# CTR-Lower-Main-Board-Rev-C-Power.net
KiCad netlist of a schematic drawn in Altium Designer
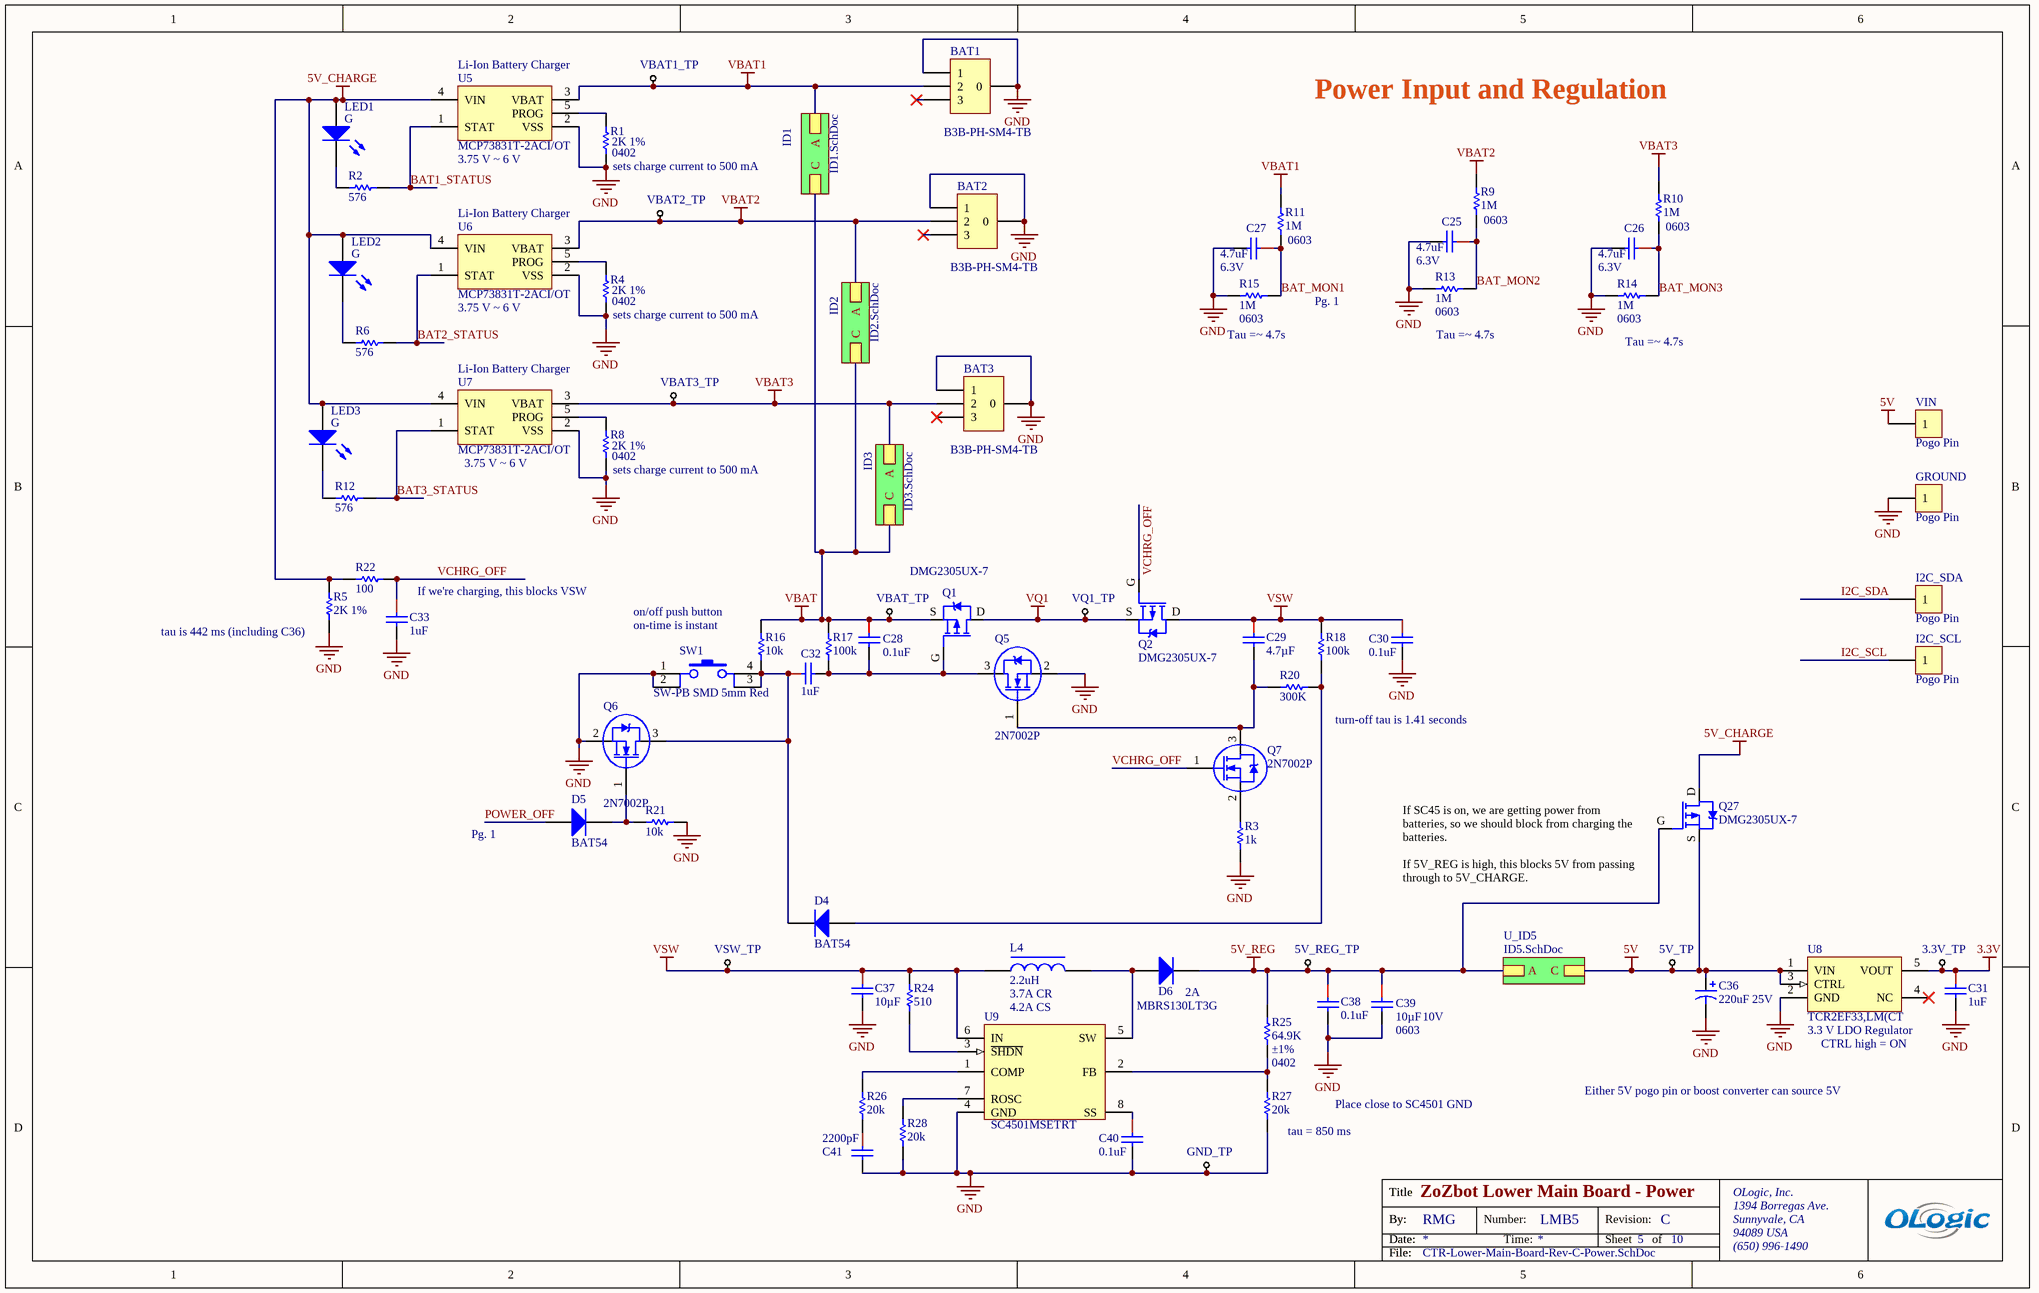
[diagram p0: CTR-Lower-Main-Board-Rev-C-Power.SchDoc]

(export (version "E")
  (design (tool "Eeschema 10.0.6"))
  (components
    (comp (ref "3.3V_TP")
      (value "Test Point")
      (footprint "TestPoint-TH 42 mil")
      (libsource (lib "OLogic-Misc") (part "TestPoint, small"))
    )
    (comp (ref "5V_REG_TP")
      (value "Test Point")
      (footprint "TestPoint-TH 42 mil")
      (libsource (lib "OLogic-Misc") (part "TestPoint, small"))
    )
    (comp (ref "5V_TP")
      (value "Test Point")
      (footprint "TestPoint-TH 42 mil")
      (libsource (lib "OLogic-Misc") (part "TestPoint, small"))
    )
    (comp (ref "BAT1")
      (value "B3B-PH-SM4-TB")
      (footprint "JST-B3B-PH-SM4-TB")
      (description "2mm Locking Header, 3-Pin")
      (fields
        (field (name "MANUFACTURER") "JST Sales America Inc")
        (field (name "MANUFACTURER PART NUMBER") "B3B-PH-SM4-TB(LF)(SN)(P)")
      )
      (libsource (lib "OLogic-Connectors") (part "JST-B3B-PH-SM4-TB"))
    )
    (comp (ref "BAT2")
      (value "B3B-PH-SM4-TB")
      (footprint "JST-B3B-PH-SM4-TB")
      (description "2mm Locking Header, 3-Pin")
      (fields
        (field (name "MANUFACTURER") "JST Sales America Inc")
        (field (name "MANUFACTURER PART NUMBER") "B3B-PH-SM4-TB(LF)(SN)(P)")
      )
      (libsource (lib "OLogic-Connectors") (part "JST-B3B-PH-SM4-TB"))
    )
    (comp (ref "BAT3")
      (value "B3B-PH-SM4-TB")
      (footprint "JST-B3B-PH-SM4-TB")
      (description "2mm Locking Header, 3-Pin")
      (fields
        (field (name "MANUFACTURER") "JST Sales America Inc")
        (field (name "MANUFACTURER PART NUMBER") "B3B-PH-SM4-TB(LF)(SN)(P)")
      )
      (libsource (lib "OLogic-Connectors") (part "JST-B3B-PH-SM4-TB"))
    )
    (comp (ref "C25")
      (value "4.7uF")
      (footprint "CAPC0402(1005)_N")
      (description "4.7uF 0402")
      (fields
        (field (name "MANUFACTURER") "Murata Electronics North America")
        (field (name "MANUFACTURER PART NUMBER") "GRM155R60J475ME47D")
        (field (name "VOLTAGE - RATED") "6.3V")
      )
      (libsource (lib "OLogic-Passive") (part "CAP CER 4.7UF 6.3V 10% X5R 0402"))
    )
    (comp (ref "C26")
      (value "4.7uF")
      (footprint "CAPC0402(1005)_N")
      (description "4.7uF 0402")
      (fields
        (field (name "MANUFACTURER") "Murata Electronics North America")
        (field (name "MANUFACTURER PART NUMBER") "GRM155R60J475ME47D")
        (field (name "VOLTAGE - RATED") "6.3V")
      )
      (libsource (lib "OLogic-Passive") (part "CAP CER 4.7UF 6.3V 10% X5R 0402"))
    )
    (comp (ref "C27")
      (value "4.7uF")
      (footprint "CAPC0402(1005)_N")
      (description "4.7uF 0402")
      (fields
        (field (name "MANUFACTURER") "Murata Electronics North America")
        (field (name "MANUFACTURER PART NUMBER") "GRM155R60J475ME47D")
        (field (name "VOLTAGE - RATED") "6.3V")
      )
      (libsource (lib "OLogic-Passive") (part "CAP CER 4.7UF 6.3V 10% X5R 0402"))
    )
    (comp (ref "C28")
      (value "0.1uF")
      (footprint "CAPC0402(1005)_N")
      (description "0.1uF 0402 50V")
      (fields
        (field (name "MANUFACTURER") "TDK Corporation")
        (field (name "MANUFACTURER PART NUMBER") "CGA2B3X7R1H104K050BB")
        (field (name "CREATOR") "osman")
      )
      (libsource (lib "OLogic-Passive") (part "CAP CER 0.1UF 50V 10% X7R 0402"))
    )
    (comp (ref "C29")
      (value "4.7UF 0603")
      (footprint "CAPC0603(1608)_L")
      (fields
        (field (name "MANUFACTURER") "Taiyo Yuden")
        (field (name "MANUFACTURER PART NUMBER") "EMK107ABJ475KA-T")
        (field (name "TOLERANCE") "±10%")
        (field (name "CAPACITANCE") "4.7µF")
        (field (name "CREATOR") "osman")
      )
      (libsource (lib "OLogic-Passive") (part "CAP CER 4.7UF 16V 10% X5R 0603"))
    )
    (comp (ref "C30")
      (value "0.1uF")
      (footprint "CAPC0402(1005)_N")
      (description "0.1uF 0402 50V")
      (fields
        (field (name "MANUFACTURER") "TDK Corporation")
        (field (name "MANUFACTURER PART NUMBER") "CGA2B3X7R1H104K050BB")
        (field (name "CREATOR") "osman")
      )
      (libsource (lib "OLogic-Passive") (part "CAP CER 0.1UF 50V 10% X7R 0402"))
    )
    (comp (ref "C31")
      (value "1uF")
      (footprint "CAPC0402(1005)_N")
      (description "1UF 0402")
      (fields
        (field (name "MANUFACTURER") "TDK Corporation")
        (field (name "MANUFACTURER PART NUMBER") "C1005X5R1C105K050BC")
      )
      (libsource (lib "OLogic-Passive") (part "CAP CER 1UF 16V 10% X5R 0402"))
    )
    (comp (ref "C32")
      (value "1uF")
      (footprint "CAPC0402(1005)_N")
      (description "1UF 0402")
      (fields
        (field (name "MANUFACTURER") "TDK Corporation")
        (field (name "MANUFACTURER PART NUMBER") "C1005X5R1C105K050BC")
      )
      (libsource (lib "OLogic-Passive") (part "CAP CER 1UF 16V 10% X5R 0402"))
    )
    (comp (ref "C33")
      (value "1uF")
      (footprint "CAPC0402(1005)_N")
      (description "1UF 0402")
      (fields
        (field (name "MANUFACTURER") "TDK Corporation")
        (field (name "MANUFACTURER PART NUMBER") "C1005X5R1C105K050BC")
      )
      (libsource (lib "OLogic-Passive") (part "CAP CER 1UF 16V 10% X5R 0402"))
    )
    (comp (ref "C36")
      (value "220uF 25V")
      (footprint "U2-P-M")
      (description "220uF 25V CAN")
      (fields
        (field (name "MANUFACTURER") "Nichicon")
        (field (name "MANUFACTURER PART NUMBER") "UWT1E221MNL1GS")
      )
      (libsource (lib "OLogic-Passive") (part "CAP ALUM 220UF 25V 20% SMD CHEAPER"))
    )
    (comp (ref "C37")
      (value "CAP 10UF 10V 10% X5R 0603")
      (footprint "CAPC0603(1608)_N")
      (description "10uF 0603")
      (fields
        (field (name "MANUFACTURER") "Samsung Electro-Mechanics America, Inc")
        (field (name "MANUFACTURER PART NUMBER") "CL10A106KP8NNNC")
        (field (name "CAPACITANCE") "10µF")
        (field (name "CREATOR") "osman")
      )
      (libsource (lib "OLogic-Passive") (part "CAP 10UF 10V 10% X5R 0603"))
    )
    (comp (ref "C38")
      (value "0.1uF")
      (footprint "CAPC0402(1005)_N")
      (description "0.1uF 0402 50V")
      (fields
        (field (name "MANUFACTURER") "TDK Corporation")
        (field (name "MANUFACTURER PART NUMBER") "CGA2B3X7R1H104K050BB")
        (field (name "CREATOR") "osman")
      )
      (libsource (lib "OLogic-Passive") (part "CAP CER 0.1UF 50V 10% X7R 0402"))
    )
    (comp (ref "C39")
      (value "CAP 10UF 10V 10% X5R 0603")
      (footprint "CAPC0603(1608)_N")
      (description "10uF 0603")
      (fields
        (field (name "MANUFACTURER") "Samsung Electro-Mechanics America, Inc")
        (field (name "MANUFACTURER PART NUMBER") "CL10A106KP8NNNC")
        (field (name "VOLTAGE - RATED") "10V")
        (field (name "PACKAGE / CASE") "0603")
        (field (name "CAPACITANCE") "10µF")
        (field (name "CREATOR") "osman")
      )
      (libsource (lib "OLogic-Passive") (part "CAP 10UF 10V 10% X5R 0603"))
    )
    (comp (ref "C40")
      (value "0.1uF")
      (footprint "CAPC0402(1005)_N")
      (description "0.1uF 0402 50V")
      (fields
        (field (name "MANUFACTURER") "TDK Corporation")
        (field (name "MANUFACTURER PART NUMBER") "CGA2B3X7R1H104K050BB")
        (field (name "CREATOR") "osman")
      )
      (libsource (lib "OLogic-Passive") (part "CAP CER 0.1UF 50V 10% X7R 0402"))
    )
    (comp (ref "C41")
      (value "2200pF")
      (footprint "CAPC0402(1005)_N")
      (description "2200pF 0402")
      (fields
        (field (name "MANUFACTURER") "Yageo")
        (field (name "MANUFACTURER PART NUMBER") "CC0402KRX7R9BB222")
        (field (name "CAPACITANCE") "2200pF")
        (field (name "CREATOR") "osman")
      )
      (libsource (lib "OLogic-Passive") (part "CAP CER 2200PF 50V 10% X7R 0402"))
    )
    (comp (ref "D4")
      (value "BAT54")
      (footprint "SOT23")
      (description "Schottky Barrier Diode")
      (fields (field (name "MANUFACTURER") "Fairchild"))
      (libsource (lib "OLogic-Diode-Opto-LED") (part "BAT54"))
    )
    (comp (ref "D5")
      (value "BAT54")
      (footprint "SOT23")
      (description "Schottky Barrier Diode")
      (fields (field (name "MANUFACTURER") "Fairchild"))
      (libsource (lib "OLogic-Diode-Opto-LED") (part "BAT54"))
    )
    (comp (ref "D6")
      (value "MBRS130LT3")
      (footprint "DO-214AA")
      (description "Schottky Barrier Rectifier 1A 30V")
      (fields
        (field (name "MANUFACTURER") "ON Semiconductor")
        (field (name "MANUFACTURER PART NUMBER") "MBRS130LT3G")
        (field (name "CURRENT - AVERAGE RECTIFIED (IO)") "2A")
      )
      (libsource (lib "OLogic-Diode-Opto-LED") (part "MBRS130LT3"))
    )
    (comp (ref "GND_TP")
      (value "Test Point")
      (footprint "TestPoint-TH 42 mil")
      (libsource (lib "OLogic-Misc") (part "TestPoint, small"))
    )
    (comp (ref "GROUND")
      (value "Pogo Pin")
      (footprint "POGO_PIN")
      (fields
        (field (name "MANUFACTURER") "Mill-Max Manufacturing Corp.")
        (field (name "MANUFACTURER PART NUMBER") "0850-0-15-20-83-14-11-0")
      )
      (libsource (lib "OLogic-Connectors") (part "0850-0-15-20-83-14-11-0"))
    )
    (comp (ref "I2C_SCL")
      (value "Pogo Pin")
      (footprint "POGO_PIN")
      (fields
        (field (name "MANUFACTURER") "Mill-Max Manufacturing Corp.")
        (field (name "MANUFACTURER PART NUMBER") "0850-0-15-20-83-14-11-0")
      )
      (libsource (lib "OLogic-Connectors") (part "0850-0-15-20-83-14-11-0"))
    )
    (comp (ref "I2C_SDA")
      (value "Pogo Pin")
      (footprint "POGO_PIN")
      (fields
        (field (name "MANUFACTURER") "Mill-Max Manufacturing Corp.")
        (field (name "MANUFACTURER PART NUMBER") "0850-0-15-20-83-14-11-0")
      )
      (libsource (lib "OLogic-Connectors") (part "0850-0-15-20-83-14-11-0"))
    )
    (comp (ref "L4")
      (value "2.2uH")
      (footprint "IND_TAIYO_NR6028")
      (description "2.2uH 6x6mm")
      (fields
        (field (name "MANUFACTURER") "Taiyo Yuden")
        (field (name "MANUFACTURER PART NUMBER") "NR6028T2R2N")
        (field (name "CURRENT RATING") "3.7A CR")
        (field (name "CURRENT - SATURATION") "4.2A CS")
      )
      (libsource (lib "OLogic-Passive") (part "INDUCTOR 2.2UH 4.2A 30% SMD"))
    )
    (comp (ref "LED1")
      (value "G")
      (footprint "SM-LED-0603")
      (description "0603 SMD GREEN LED")
      (fields
        (field (name "MANUFACTURER") "Lite-On Inc")
        (field (name "MANUFACTURER PART NUMBER") "LTST-C191KGKT")
      )
      (libsource (lib "OLogic-Diode-Opto-LED") (part "LED GREEN CLEAR THIN 0603 SMD"))
    )
    (comp (ref "LED2")
      (value "G")
      (footprint "SM-LED-0603")
      (description "0603 SMD GREEN LED")
      (fields
        (field (name "MANUFACTURER") "Lite-On Inc")
        (field (name "MANUFACTURER PART NUMBER") "LTST-C191KGKT")
      )
      (libsource (lib "OLogic-Diode-Opto-LED") (part "LED GREEN CLEAR THIN 0603 SMD"))
    )
    (comp (ref "LED3")
      (value "G")
      (footprint "SM-LED-0603")
      (description "0603 SMD GREEN LED")
      (fields
        (field (name "MANUFACTURER") "Lite-On Inc")
        (field (name "MANUFACTURER PART NUMBER") "LTST-C191KGKT")
      )
      (libsource (lib "OLogic-Diode-Opto-LED") (part "LED GREEN CLEAR THIN 0603 SMD"))
    )
    (comp (ref "Q1")
      (value "DMG2305UX")
      (footprint "DMG2305UX-7")
      (description "MOSFET P-CH 20V 4.2A SOT23")
      (fields
        (field (name "MANUFACTURER") "Diodes Incorporated")
        (field (name "MANUFACTURER PART NUMBER") "DMG2305UX-7")
        (field (name "CREATOR") "osman")
      )
      (libsource (lib "OLogic-Trans-Drivers") (part "DMG2305UX"))
    )
    (comp (ref "Q2")
      (value "DMG2305UX")
      (footprint "DMG2305UX-7")
      (description "MOSFET P-CH 20V 4.2A SOT23")
      (fields
        (field (name "MANUFACTURER") "Diodes Incorporated")
        (field (name "MANUFACTURER PART NUMBER") "DMG2305UX-7")
        (field (name "CREATOR") "osman")
      )
      (libsource (lib "OLogic-Trans-Drivers") (part "DMG2305UX"))
    )
    (comp (ref "Q5")
      (value "2N7002P")
      (footprint "SOT23")
      (description "MOSFET N-CH 60V 0.36A SOT-23")
      (fields
        (field (name "MANUFACTURER") "Nexperia USA Inc.")
        (field (name "MANUFACTURER PART NUMBER") "2N7002P,235")
      )
      (libsource (lib "OLogic-Trans-Drivers") (part "2N7002P"))
    )
    (comp (ref "Q6")
      (value "2N7002P")
      (footprint "SOT23")
      (description "MOSFET N-CH 60V 0.36A SOT-23")
      (fields
        (field (name "MANUFACTURER") "Nexperia USA Inc.")
        (field (name "MANUFACTURER PART NUMBER") "2N7002P,235")
      )
      (libsource (lib "") (part "2N7002P_1"))
    )
    (comp (ref "Q7")
      (value "2N7002P")
      (footprint "SOT23")
      (description "MOSFET N-CH 60V 0.36A SOT-23")
      (fields
        (field (name "MANUFACTURER") "Nexperia USA Inc.")
        (field (name "MANUFACTURER PART NUMBER") "2N7002P,235")
      )
      (libsource (lib "") (part "2N7002P_2"))
    )
    (comp (ref "Q27")
      (value "DMG2305UX")
      (footprint "DMG2305UX-7")
      (description "MOSFET P-CH 20V 4.2A SOT23")
      (fields
        (field (name "MANUFACTURER") "Diodes Incorporated")
        (field (name "MANUFACTURER PART NUMBER") "DMG2305UX-7")
        (field (name "CREATOR") "osman")
      )
      (libsource (lib "OLogic-Trans-Drivers") (part "DMG2305UX"))
    )
    (comp (ref "R1")
      (value "2K 1%")
      (footprint "RESC0402(1005)_N")
      (description "2K 1% 0402")
      (fields
        (field (name "MANUFACTURER") "Panasonic Electronic Components")
        (field (name "MANUFACTURER PART NUMBER") "ERJ-2RKF2001X")
        (field (name "PACKAGE / CASE") "0402")
      )
      (libsource (lib "OLogic-Passive") (part "RES 2K OHM 1% 1/10W 0402"))
    )
    (comp (ref "R2")
      (value "576")
      (footprint "RESC0402(1005)_N")
      (description "575 0402")
      (fields
        (field (name "MANUFACTURER") "Panasonic Electronic Components")
        (field (name "MANUFACTURER PART NUMBER") "ERJ-2RKF5760X")
        (field (name "RESISTANCE (OHMS)") "576")
        (field (name "CREATOR") "osman")
      )
      (libsource (lib "OLogic-Passive") (part "RES 576 OHM 1% 1/10W 0402"))
    )
    (comp (ref "R3")
      (value "1K")
      (footprint "RESC0402(1005)_N")
      (description "1K 0402")
      (fields
        (field (name "MANUFACTURER") "Panasonic Electronic Components")
        (field (name "MANUFACTURER PART NUMBER") "ERJ-2RKF1001X")
        (field (name "RESISTANCE (OHMS)") "1k")
        (field (name "CREATOR") "osman")
      )
      (libsource (lib "OLogic-Passive") (part "RES 1K OHM 1% 1/10W 0402"))
    )
    (comp (ref "R4")
      (value "2K 1%")
      (footprint "RESC0402(1005)_N")
      (description "2K 1% 0402")
      (fields
        (field (name "MANUFACTURER") "Panasonic Electronic Components")
        (field (name "MANUFACTURER PART NUMBER") "ERJ-2RKF2001X")
        (field (name "PACKAGE / CASE") "0402")
      )
      (libsource (lib "OLogic-Passive") (part "RES 2K OHM 1% 1/10W 0402"))
    )
    (comp (ref "R5")
      (value "2K 1%")
      (footprint "RESC0402(1005)_N")
      (description "2K 1% 0402")
      (fields
        (field (name "MANUFACTURER") "Panasonic Electronic Components")
        (field (name "MANUFACTURER PART NUMBER") "ERJ-2RKF2001X")
      )
      (libsource (lib "OLogic-Passive") (part "RES 2K OHM 1% 1/10W 0402"))
    )
    (comp (ref "R6")
      (value "576")
      (footprint "RESC0402(1005)_N")
      (description "575 0402")
      (fields
        (field (name "MANUFACTURER") "Panasonic Electronic Components")
        (field (name "MANUFACTURER PART NUMBER") "ERJ-2RKF5760X")
        (field (name "RESISTANCE (OHMS)") "576")
        (field (name "CREATOR") "osman")
      )
      (libsource (lib "OLogic-Passive") (part "RES 576 OHM 1% 1/10W 0402"))
    )
    (comp (ref "R8")
      (value "2K 1%")
      (footprint "RESC0402(1005)_N")
      (description "2K 1% 0402")
      (fields
        (field (name "MANUFACTURER") "Panasonic Electronic Components")
        (field (name "MANUFACTURER PART NUMBER") "ERJ-2RKF2001X")
        (field (name "PACKAGE / CASE") "0402")
      )
      (libsource (lib "OLogic-Passive") (part "RES 2K OHM 1% 1/10W 0402"))
    )
    (comp (ref "R9")
      (value "1M")
      (footprint "RESC0603(1608)_N")
      (description "1M 0603")
      (fields
        (field (name "MANUFACTURER") "Panasonic Electronic Components")
        (field (name "MANUFACTURER PART NUMBER") "ERJ-3EKF1004V")
        (field (name "SUPPLIER DEVICE PACKAGE") "0603")
      )
      (libsource (lib "OLogic-Passive") (part "RES 1M OHM 1/10W 1% 0603 SMD"))
    )
    (comp (ref "R10")
      (value "1M")
      (footprint "RESC0603(1608)_N")
      (description "1M 0603")
      (fields
        (field (name "MANUFACTURER") "Panasonic Electronic Components")
        (field (name "MANUFACTURER PART NUMBER") "ERJ-3EKF1004V")
        (field (name "SUPPLIER DEVICE PACKAGE") "0603")
      )
      (libsource (lib "OLogic-Passive") (part "RES 1M OHM 1/10W 1% 0603 SMD"))
    )
    (comp (ref "R11")
      (value "1M")
      (footprint "RESC0603(1608)_N")
      (description "1M 0603")
      (fields
        (field (name "MANUFACTURER") "Panasonic Electronic Components")
        (field (name "MANUFACTURER PART NUMBER") "ERJ-3EKF1004V")
        (field (name "SUPPLIER DEVICE PACKAGE") "0603")
      )
      (libsource (lib "OLogic-Passive") (part "RES 1M OHM 1/10W 1% 0603 SMD"))
    )
    (comp (ref "R12")
      (value "576")
      (footprint "RESC0402(1005)_N")
      (description "575 0402")
      (fields
        (field (name "MANUFACTURER") "Panasonic Electronic Components")
        (field (name "MANUFACTURER PART NUMBER") "ERJ-2RKF5760X")
        (field (name "RESISTANCE (OHMS)") "576")
        (field (name "CREATOR") "osman")
      )
      (libsource (lib "OLogic-Passive") (part "RES 576 OHM 1% 1/10W 0402"))
    )
    (comp (ref "R13")
      (value "1M")
      (footprint "RESC0603(1608)_N")
      (description "1M 0603")
      (fields
        (field (name "MANUFACTURER") "Panasonic Electronic Components")
        (field (name "MANUFACTURER PART NUMBER") "ERJ-3EKF1004V")
        (field (name "SUPPLIER DEVICE PACKAGE") "0603")
      )
      (libsource (lib "OLogic-Passive") (part "RES 1M OHM 1/10W 1% 0603 SMD"))
    )
    (comp (ref "R14")
      (value "1M")
      (footprint "RESC0603(1608)_N")
      (description "1M 0603")
      (fields
        (field (name "MANUFACTURER") "Panasonic Electronic Components")
        (field (name "MANUFACTURER PART NUMBER") "ERJ-3EKF1004V")
        (field (name "SUPPLIER DEVICE PACKAGE") "0603")
      )
      (libsource (lib "OLogic-Passive") (part "RES 1M OHM 1/10W 1% 0603 SMD"))
    )
    (comp (ref "R15")
      (value "1M")
      (footprint "RESC0603(1608)_N")
      (description "1M 0603")
      (fields
        (field (name "MANUFACTURER") "Panasonic Electronic Components")
        (field (name "MANUFACTURER PART NUMBER") "ERJ-3EKF1004V")
        (field (name "SUPPLIER DEVICE PACKAGE") "0603")
      )
      (libsource (lib "OLogic-Passive") (part "RES 1M OHM 1/10W 1% 0603 SMD"))
    )
    (comp (ref "R16")
      (value "10K")
      (footprint "RESC0402(1005)_N")
      (description "10K 0402")
      (fields
        (field (name "MANUFACTURER") "Panasonic Electronic Components")
        (field (name "MANUFACTURER PART NUMBER") "ERJ-2RKF1002X")
        (field (name "RESISTANCE (OHMS)") "10k")
        (field (name "CREATOR") "osman")
      )
      (libsource (lib "OLogic-Passive") (part "RES 10K OHM 1% 1/10W 0402"))
    )
    (comp (ref "R17")
      (value "100K 0402")
      (footprint "RESC0402(1005)_N")
      (fields
        (field (name "MANUFACTURER") "Panasonic Electronic Components")
        (field (name "MANUFACTURER PART NUMBER") "ERJ-2RKF1003X")
        (field (name "TOLERANCE") "±1%")
        (field (name "RESISTANCE (OHMS)") "100k")
        (field (name "CREATOR") "osman")
      )
      (libsource (lib "OLogic-Passive") (part "RES 100K OHM 1% 1/10W 0402"))
    )
    (comp (ref "R18")
      (value "100K 0402")
      (footprint "RESC0402(1005)_N")
      (fields
        (field (name "MANUFACTURER") "Panasonic Electronic Components")
        (field (name "MANUFACTURER PART NUMBER") "ERJ-2RKF1003X")
        (field (name "TOLERANCE") "±1%")
        (field (name "RESISTANCE (OHMS)") "100k")
        (field (name "CREATOR") "osman")
      )
      (libsource (lib "OLogic-Passive") (part "RES 100K OHM 1% 1/10W 0402"))
    )
    (comp (ref "R20")
      (value "300K")
      (footprint "RESC0402(1005)_N")
      (description "300K 0402")
      (fields
        (field (name "MANUFACTURER") "Panasonic Electronic Components")
        (field (name "MANUFACTURER PART NUMBER") "ERJ-2RKF3003X")
      )
      (libsource (lib "OLogic-Passive") (part "RES 300K OHM 1% 1/10W 0402"))
    )
    (comp (ref "R21")
      (value "10K")
      (footprint "RESC0402(1005)_N")
      (description "10K 0402")
      (fields
        (field (name "MANUFACTURER") "Panasonic Electronic Components")
        (field (name "MANUFACTURER PART NUMBER") "ERJ-2RKF1002X")
        (field (name "RESISTANCE (OHMS)") "10k")
        (field (name "CREATOR") "osman")
      )
      (libsource (lib "OLogic-Passive") (part "RES 10K OHM 1% 1/10W 0402"))
    )
    (comp (ref "R22")
      (value "100 0402")
      (footprint "RESC0402(1005)_N")
      (fields
        (field (name "MANUFACTURER") "Panasonic Electronic Components")
        (field (name "MANUFACTURER PART NUMBER") "ERJ-2RKF1000X")
        (field (name "TOLERANCE") "±1%")
        (field (name "RESISTANCE (OHMS)") "100")
        (field (name "CREATOR") "osman")
      )
      (libsource (lib "OLogic-Passive") (part "RES 100 OHM 1% 1/10W 0402"))
    )
    (comp (ref "R24")
      (value "510")
      (footprint "RESC0603(1608)_N")
      (description "510 0603")
      (fields
        (field (name "MANUFACTURER") "Panasonic Electronic Components")
        (field (name "MANUFACTURER PART NUMBER") "ERJ-3EKF5100V")
      )
      (libsource (lib "OLogic-Passive") (part "RES 510 OHM 1/10W 1% 0603 SMD"))
    )
    (comp (ref "R25")
      (value "64.9K")
      (footprint "RESC0402(1005)_N")
      (description "RES 64.9K OHM 1% 1/10W 0402")
      (fields
        (field (name "MANUFACTURER") "Panasonic Electronic Components")
        (field (name "MANUFACTURER PART NUMBER") "ERJ-2RKF6492X")
        (field (name "TOLERANCE") "±1%")
        (field (name "SUPPLIER DEVICE PACKAGE") "0402")
      )
      (libsource (lib "OLogic-Passive") (part "RES 64.9K OHM 1% 1/10W 0402"))
    )
    (comp (ref "R26")
      (value "20K 0402")
      (footprint "RESC0402(1005)_N")
      (fields
        (field (name "MANUFACTURER") "Panasonic Electronic Components")
        (field (name "MANUFACTURER PART NUMBER") "ERJ-2RKF2002X")
        (field (name "RESISTANCE (OHMS)") "20k")
        (field (name "TOLERANCE") "±1%")
      )
      (libsource (lib "OLogic-Passive") (part "RES 20K OHM 1% 1/10W 0402"))
    )
    (comp (ref "R27")
      (value "20K 0402")
      (footprint "RESC0402(1005)_N")
      (fields
        (field (name "MANUFACTURER") "Panasonic Electronic Components")
        (field (name "MANUFACTURER PART NUMBER") "ERJ-2RKF2002X")
        (field (name "TOLERANCE") "±1%")
        (field (name "RESISTANCE (OHMS)") "20k")
      )
      (libsource (lib "OLogic-Passive") (part "RES 20K OHM 1% 1/10W 0402"))
    )
    (comp (ref "R28")
      (value "20K 0402")
      (footprint "RESC0402(1005)_N")
      (fields
        (field (name "MANUFACTURER") "Panasonic Electronic Components")
        (field (name "MANUFACTURER PART NUMBER") "ERJ-2RKF2002X")
        (field (name "RESISTANCE (OHMS)") "20k")
        (field (name "TOLERANCE") "±1%")
      )
      (libsource (lib "OLogic-Passive") (part "RES 20K OHM 1% 1/10W 0402"))
    )
    (comp (ref "SW1")
      (value "SW-PB SMD 5mm Red")
      (footprint "SW TACT Red 6mm x 6mm")
      (description "SWITCH TACTILE SPST-NO 0.05A 12V")
      (fields
        (field (name "MANUFACTURER") "C&K Components")
        (field (name "MANUFACTURER PART NUMBER") "PTS645SK50SMTR92 LFS")
        (field (name "PUBLISHER") "Altium Limited")
      )
      (libsource (lib "OLogic-Switches") (part "SW-PB SMD 5mm Red"))
    )
    (comp (ref "U5")
      (value "Li-Ion Battery Charger")
      (footprint "SOT23-5")
      (fields
        (field (name "MPN") "MCP73831T")
        (field (name "MANUFACTURER") "Microchip")
        (field (name "MANUFACTURER PART NUMBER") "MCP73831T-2ACI/OT")
        (field (name "VOLTAGE - SUPPLY") "3.75 V ~ 6 V")
      )
      (libsource (lib "OLogic-Misc") (part "MCP73831"))
    )
    (comp (ref "U6")
      (value "Li-Ion Battery Charger")
      (footprint "SOT23-5")
      (fields
        (field (name "MPN") "MCP73831T")
        (field (name "MANUFACTURER") "Microchip")
        (field (name "MANUFACTURER PART NUMBER") "MCP73831T-2ACI/OT")
        (field (name "VOLTAGE - SUPPLY") "3.75 V ~ 6 V")
      )
      (libsource (lib "OLogic-Misc") (part "MCP73831"))
    )
    (comp (ref "U7")
      (value "Li-Ion Battery Charger")
      (footprint "SOT23-5")
      (fields
        (field (name "MPN") "MCP73831T")
        (field (name "MANUFACTURER") "Microchip")
        (field (name "MANUFACTURER PART NUMBER") "MCP73831T-2ACI/OT")
        (field (name "VOLTAGE - SUPPLY") "3.75 V ~ 6 V")
      )
      (libsource (lib "OLogic-Misc") (part "MCP73831"))
    )
    (comp (ref "U8")
      (value "3.3 V LDO Regulator")
      (footprint "TCRFEF")
      (description "IC REG LDO 3.3V 0.2A ESV")
      (fields
        (field (name "MANUFACTURER") "Toshiba Semiconductor and Storage")
        (field (name "MANUFACTURER PART NUMBER") "TCR2EF33,LM(CT")
        (field (name "CREATOR") "osman")
      )
      (libsource (lib "OLogic-Reg-Convert") (part "TCR2EF33"))
    )
    (comp (ref "U9")
      (value "SC4501")
      (footprint "SC4501")
      (description "2A Switching Step-Up Regulator")
      (fields
        (field (name "MANUFACTURER") "Semtech Corporation")
        (field (name "MANUFACTURER PART NUMBER") "SC4501MSETRT")
      )
      (libsource (lib "OLogic-Reg-Convert") (part "SC4501"))
    )
    (comp (ref "VBAT1_TP")
      (value "Test Point")
      (footprint "TestPoint-TH 42 mil")
      (libsource (lib "OLogic-Misc") (part "TestPoint, small"))
    )
    (comp (ref "VBAT2_TP")
      (value "Test Point")
      (footprint "TestPoint-TH 42 mil")
      (libsource (lib "OLogic-Misc") (part "TestPoint, small"))
    )
    (comp (ref "VBAT3_TP")
      (value "Test Point")
      (footprint "TestPoint-TH 42 mil")
      (libsource (lib "OLogic-Misc") (part "TestPoint, small"))
    )
    (comp (ref "VBAT_TP")
      (value "Test Point")
      (footprint "TestPoint-TH 42 mil")
      (libsource (lib "OLogic-Misc") (part "TestPoint, small"))
    )
    (comp (ref "VIN")
      (value "Pogo Pin")
      (footprint "POGO_PIN")
      (fields
        (field (name "MANUFACTURER") "Mill-Max Manufacturing Corp.")
        (field (name "MANUFACTURER PART NUMBER") "0850-0-15-20-83-14-11-0")
      )
      (libsource (lib "OLogic-Connectors") (part "0850-0-15-20-83-14-11-0"))
    )
    (comp (ref "VQ1_TP")
      (value "Test Point")
      (footprint "TestPoint-TH 42 mil")
      (libsource (lib "OLogic-Misc") (part "TestPoint, small"))
    )
    (comp (ref "VSW_TP")
      (value "Test Point")
      (footprint "TestPoint-TH 42 mil")
      (libsource (lib "OLogic-Misc") (part "TestPoint, small"))
    )
  )
  (nets
    (net (code "1") (name "/BAT1_STATUS") (class "Default")
      (node (ref "R2") (pin "2") (pinfunction "2_2") (pintype "passive"))
      (node (ref "U5") (pin "1") (pinfunction "STAT_1") (pintype "passive"))
    )
    (net (code "2") (name "/BAT2_STATUS") (class "Default")
      (node (ref "R6") (pin "2") (pinfunction "2_2") (pintype "passive"))
      (node (ref "U6") (pin "1") (pinfunction "STAT_1") (pintype "passive"))
    )
    (net (code "3") (name "/BAT3_STATUS") (class "Default")
      (node (ref "R12") (pin "2") (pinfunction "2_2") (pintype "passive"))
      (node (ref "U7") (pin "1") (pinfunction "STAT_1") (pintype "passive"))
    )
    (net (code "4") (name "/BAT_MON1") (class "Default")
      (node (ref "C27") (pin "1") (pinfunction "1_1") (pintype "passive"))
      (node (ref "R11") (pin "1") (pinfunction "1_1") (pintype "passive"))
      (node (ref "R15") (pin "1") (pinfunction "1_1") (pintype "passive"))
    )
    (net (code "5") (name "/BAT_MON2") (class "Default")
      (node (ref "C25") (pin "1") (pinfunction "1_1") (pintype "passive"))
      (node (ref "R13") (pin "1") (pinfunction "1_1") (pintype "passive"))
      (node (ref "R9") (pin "1") (pinfunction "1_1") (pintype "passive"))
    )
    (net (code "6") (name "/BAT_MON3") (class "Default")
      (node (ref "C26") (pin "1") (pinfunction "1_1") (pintype "passive"))
      (node (ref "R10") (pin "1") (pinfunction "1_1") (pintype "passive"))
      (node (ref "R14") (pin "1") (pinfunction "1_1") (pintype "passive"))
    )
    (net (code "7") (name "/I2C_SCL") (class "Default")
      (node (ref "I2C_SCL") (pin "1") (pinfunction "1_1") (pintype "passive"))
    )
    (net (code "8") (name "/I2C_SDA") (class "Default")
      (node (ref "I2C_SDA") (pin "1") (pinfunction "1_1") (pintype "passive"))
    )
    (net (code "9") (name "/POWER_OFF") (class "Default")
      (node (ref "D5") (pin "1") (pinfunction "A_1") (pintype "passive"))
    )
    (net (code "10") (name "/VCHRG_OFF") (class "Default")
      (node (ref "C33") (pin "1") (pinfunction "1_1") (pintype "passive"))
      (node (ref "Q2") (pin "G") (pinfunction "G_G") (pintype "passive"))
      (node (ref "Q7") (pin "1") (pinfunction "G_1") (pintype "passive"))
      (node (ref "R22") (pin "1") (pinfunction "1_1") (pintype "passive"))
    )
    (net (code "11") (name "3.3V") (class "Default")
      (node (ref "3.3V_TP") (pin "1") (pinfunction "1_1") (pintype "passive"))
      (node (ref "C31") (pin "1") (pinfunction "1_1") (pintype "passive"))
      (node (ref "U8") (pin "5") (pinfunction "VOUT_5") (pintype "power_in"))
    )
    (net (code "12") (name "5V") (class "Default")
      (node (ref "5V_TP") (pin "1") (pinfunction "1_1") (pintype "passive"))
      (node (ref "C36") (pin "1") (pinfunction "1_1") (pintype "passive"))
      (node (ref "Q27") (pin "S") (pinfunction "S_S") (pintype "passive"))
      (node (ref "U8") (pin "1") (pinfunction "VIN_1") (pintype "power_in"))
      (node (ref "U8") (pin "3") (pinfunction "CTRL_3") (pintype "input"))
      (node (ref "VIN") (pin "1") (pinfunction "1_1") (pintype "passive"))
    )
    (net (code "13") (name "5V_CHARGE") (class "Default")
      (node (ref "LED1") (pin "1") (pinfunction "1_1") (pintype "passive"))
      (node (ref "LED2") (pin "1") (pinfunction "1_1") (pintype "passive"))
      (node (ref "LED3") (pin "1") (pinfunction "1_1") (pintype "passive"))
      (node (ref "Q27") (pin "D") (pinfunction "D_D") (pintype "passive"))
      (node (ref "R22") (pin "2") (pinfunction "2_2") (pintype "passive"))
      (node (ref "R5") (pin "2") (pinfunction "2_2") (pintype "passive"))
      (node (ref "U5") (pin "4") (pinfunction "VIN_4") (pintype "passive"))
      (node (ref "U6") (pin "4") (pinfunction "VIN_4") (pintype "passive"))
      (node (ref "U7") (pin "4") (pinfunction "VIN_4") (pintype "passive"))
    )
    (net (code "14") (name "5V_REG") (class "Default")
      (node (ref "5V_REG_TP") (pin "1") (pinfunction "1_1") (pintype "passive"))
      (node (ref "C38") (pin "1") (pinfunction "1_1") (pintype "passive"))
      (node (ref "C39") (pin "1") (pinfunction "1_1") (pintype "passive"))
      (node (ref "D6") (pin "2") (pinfunction "K_2") (pintype "passive"))
      (node (ref "Q27") (pin "G") (pinfunction "G_G") (pintype "passive"))
      (node (ref "R25") (pin "2") (pinfunction "2_2") (pintype "passive"))
    )
    (net (code "15") (name "GND") (class "Default")
      (node (ref "BAT1") (pin "0") (pinfunction "0_0") (pintype "passive"))
      (node (ref "BAT1") (pin "1") (pinfunction "1_1") (pintype "passive"))
      (node (ref "BAT2") (pin "0") (pinfunction "0_0") (pintype "passive"))
      (node (ref "BAT2") (pin "1") (pinfunction "1_1") (pintype "passive"))
      (node (ref "BAT3") (pin "0") (pinfunction "0_0") (pintype "passive"))
      (node (ref "BAT3") (pin "1") (pinfunction "1_1") (pintype "passive"))
      (node (ref "C25") (pin "2") (pinfunction "2_2") (pintype "passive"))
      (node (ref "C26") (pin "2") (pinfunction "2_2") (pintype "passive"))
      (node (ref "C27") (pin "2") (pinfunction "2_2") (pintype "passive"))
      (node (ref "C30") (pin "2") (pinfunction "2_2") (pintype "passive"))
      (node (ref "C31") (pin "2") (pinfunction "2_2") (pintype "passive"))
      (node (ref "C33") (pin "2") (pinfunction "2_2") (pintype "passive"))
      (node (ref "C36") (pin "2") (pinfunction "2_2") (pintype "passive"))
      (node (ref "C37") (pin "2") (pinfunction "2_2") (pintype "passive"))
      (node (ref "C38") (pin "2") (pinfunction "2_2") (pintype "passive"))
      (node (ref "C39") (pin "2") (pinfunction "2_2") (pintype "passive"))
      (node (ref "C40") (pin "2") (pinfunction "2_2") (pintype "passive"))
      (node (ref "C41") (pin "2") (pinfunction "2_2") (pintype "passive"))
      (node (ref "GND_TP") (pin "1") (pinfunction "1_1") (pintype "passive"))
      (node (ref "GROUND") (pin "1") (pinfunction "1_1") (pintype "passive"))
      (node (ref "Q5") (pin "2") (pinfunction "S_2") (pintype "passive"))
      (node (ref "Q6") (pin "2") (pinfunction "S_2") (pintype "passive"))
      (node (ref "R1") (pin "1") (pinfunction "1_1") (pintype "passive"))
      (node (ref "R13") (pin "2") (pinfunction "2_2") (pintype "passive"))
      (node (ref "R14") (pin "2") (pinfunction "2_2") (pintype "passive"))
      (node (ref "R15") (pin "2") (pinfunction "2_2") (pintype "passive"))
      (node (ref "R21") (pin "1") (pinfunction "1_1") (pintype "passive"))
      (node (ref "R27") (pin "1") (pinfunction "1_1") (pintype "passive"))
      (node (ref "R28") (pin "2") (pinfunction "2_2") (pintype "passive"))
      (node (ref "R3") (pin "1") (pinfunction "1_1") (pintype "passive"))
      (node (ref "R4") (pin "1") (pinfunction "1_1") (pintype "passive"))
      (node (ref "R5") (pin "1") (pinfunction "1_1") (pintype "passive"))
      (node (ref "R8") (pin "1") (pinfunction "1_1") (pintype "passive"))
      (node (ref "SW1") (pin "1") (pinfunction "1_1") (pintype "passive"))
      (node (ref "SW1") (pin "2") (pinfunction "2_2") (pintype "passive"))
      (node (ref "U5") (pin "2") (pinfunction "VSS_2") (pintype "passive"))
      (node (ref "U6") (pin "2") (pinfunction "VSS_2") (pintype "passive"))
      (node (ref "U7") (pin "2") (pinfunction "VSS_2") (pintype "passive"))
      (node (ref "U8") (pin "2") (pinfunction "GND_2") (pintype "power_in"))
      (node (ref "U9") (pin "4") (pinfunction "GND_4") (pintype "power_in"))
    )
    (net (code "16") (name "Net-(C41-Pad1)") (class "Default")
      (node (ref "C41") (pin "1") (pinfunction "1_1") (pintype "passive"))
      (node (ref "R26") (pin "2") (pinfunction "2_2") (pintype "passive"))
    )
    (net (code "17") (name "Net-(D4-A)") (class "Default")
      (node (ref "D4") (pin "1") (pinfunction "A_1") (pintype "passive"))
      (node (ref "R18") (pin "1") (pinfunction "1_1") (pintype "passive"))
      (node (ref "R20") (pin "1") (pinfunction "1_1") (pintype "passive"))
    )
    (net (code "18") (name "Net-(D4-K)") (class "Default")
      (node (ref "C32") (pin "1") (pinfunction "1_1") (pintype "passive"))
      (node (ref "D4") (pin "3") (pinfunction "K_3") (pintype "passive"))
      (node (ref "Q6") (pin "3") (pinfunction "D_3") (pintype "passive"))
      (node (ref "R16") (pin "1") (pinfunction "1_1") (pintype "passive"))
      (node (ref "SW1") (pin "3") (pinfunction "3_3") (pintype "passive"))
      (node (ref "SW1") (pin "4") (pinfunction "4_4") (pintype "passive"))
    )
    (net (code "19") (name "Net-(D5-K)") (class "Default")
      (node (ref "D5") (pin "3") (pinfunction "K_3") (pintype "passive"))
      (node (ref "Q6") (pin "1") (pinfunction "G_1") (pintype "passive"))
      (node (ref "R21") (pin "2") (pinfunction "2_2") (pintype "passive"))
    )
    (net (code "20") (name "Net-(D6-A)") (class "Default")
      (node (ref "D6") (pin "1") (pinfunction "A_1") (pintype "passive"))
      (node (ref "L4") (pin "2") (pinfunction "2_2") (pintype "passive"))
      (node (ref "U9") (pin "5") (pinfunction "SW_5") (pintype "passive"))
    )
    (net (code "21") (name "Net-(LED1-Pad2)") (class "Default")
      (node (ref "LED1") (pin "2") (pinfunction "2_2") (pintype "passive"))
      (node (ref "R2") (pin "1") (pinfunction "1_1") (pintype "passive"))
    )
    (net (code "22") (name "Net-(LED2-Pad2)") (class "Default")
      (node (ref "LED2") (pin "2") (pinfunction "2_2") (pintype "passive"))
      (node (ref "R6") (pin "1") (pinfunction "1_1") (pintype "passive"))
    )
    (net (code "23") (name "Net-(LED3-Pad2)") (class "Default")
      (node (ref "LED3") (pin "2") (pinfunction "2_2") (pintype "passive"))
      (node (ref "R12") (pin "1") (pinfunction "1_1") (pintype "passive"))
    )
    (net (code "24") (name "Net-(Q5-D)") (class "Default")
      (node (ref "C28") (pin "2") (pinfunction "2_2") (pintype "passive"))
      (node (ref "C32") (pin "2") (pinfunction "2_2") (pintype "passive"))
      (node (ref "Q1") (pin "G") (pinfunction "G_G") (pintype "passive"))
      (node (ref "Q5") (pin "3") (pinfunction "D_3") (pintype "passive"))
      (node (ref "R17") (pin "1") (pinfunction "1_1") (pintype "passive"))
    )
    (net (code "25") (name "Net-(Q5-G)") (class "Default")
      (node (ref "C29") (pin "2") (pinfunction "2_2") (pintype "passive"))
      (node (ref "Q5") (pin "1") (pinfunction "G_1") (pintype "passive"))
      (node (ref "Q7") (pin "3") (pinfunction "D_3") (pintype "passive"))
      (node (ref "R20") (pin "2") (pinfunction "2_2") (pintype "passive"))
    )
    (net (code "26") (name "Net-(Q7-S)") (class "Default")
      (node (ref "Q7") (pin "2") (pinfunction "S_2") (pintype "passive"))
      (node (ref "R3") (pin "2") (pinfunction "2_2") (pintype "passive"))
    )
    (net (code "27") (name "Net-(U5-PROG)") (class "Default")
      (node (ref "R1") (pin "2") (pinfunction "2_2") (pintype "passive"))
      (node (ref "U5") (pin "5") (pinfunction "PROG_5") (pintype "passive"))
    )
    (net (code "28") (name "Net-(U6-PROG)") (class "Default")
      (node (ref "R4") (pin "2") (pinfunction "2_2") (pintype "passive"))
      (node (ref "U6") (pin "5") (pinfunction "PROG_5") (pintype "passive"))
    )
    (net (code "29") (name "Net-(U7-PROG)") (class "Default")
      (node (ref "R8") (pin "2") (pinfunction "2_2") (pintype "passive"))
      (node (ref "U7") (pin "5") (pinfunction "PROG_5") (pintype "passive"))
    )
    (net (code "30") (name "Net-(U9-COMP)") (class "Default")
      (node (ref "R26") (pin "1") (pinfunction "1_1") (pintype "passive"))
      (node (ref "U9") (pin "1") (pinfunction "COMP_1") (pintype "passive"))
    )
    (net (code "31") (name "Net-(U9-FB)") (class "Default")
      (node (ref "R25") (pin "1") (pinfunction "1_1") (pintype "passive"))
      (node (ref "R27") (pin "2") (pinfunction "2_2") (pintype "passive"))
      (node (ref "U9") (pin "2") (pinfunction "FB_2") (pintype "passive"))
    )
    (net (code "32") (name "Net-(U9-ROSC)") (class "Default")
      (node (ref "R28") (pin "1") (pinfunction "1_1") (pintype "passive"))
      (node (ref "U9") (pin "7") (pinfunction "ROSC_7") (pintype "passive"))
    )
    (net (code "33") (name "Net-(U9-SS)") (class "Default")
      (node (ref "C40") (pin "1") (pinfunction "1_1") (pintype "passive"))
      (node (ref "U9") (pin "8") (pinfunction "SS_8") (pintype "passive"))
    )
    (net (code "34") (name "Net-(U9-~{SHDN})") (class "Default")
      (node (ref "R24") (pin "1") (pinfunction "1_1") (pintype "passive"))
      (node (ref "U9") (pin "3") (pinfunction "~{SHDN}_3") (pintype "input"))
    )
    (net (code "35") (name "VBAT") (class "Default")
      (node (ref "C28") (pin "1") (pinfunction "1_1") (pintype "passive"))
      (node (ref "Q1") (pin "S") (pinfunction "S_S") (pintype "passive"))
      (node (ref "R16") (pin "2") (pinfunction "2_2") (pintype "passive"))
      (node (ref "R17") (pin "2") (pinfunction "2_2") (pintype "passive"))
      (node (ref "VBAT_TP") (pin "1") (pinfunction "1_1") (pintype "passive"))
    )
    (net (code "36") (name "VBAT1") (class "Default")
      (node (ref "BAT1") (pin "2") (pinfunction "2_2") (pintype "passive"))
      (node (ref "R11") (pin "2") (pinfunction "2_2") (pintype "passive"))
      (node (ref "U5") (pin "3") (pinfunction "VBAT_3") (pintype "passive"))
      (node (ref "VBAT1_TP") (pin "1") (pinfunction "1_1") (pintype "passive"))
    )
    (net (code "37") (name "VBAT2") (class "Default")
      (node (ref "BAT2") (pin "2") (pinfunction "2_2") (pintype "passive"))
      (node (ref "R9") (pin "2") (pinfunction "2_2") (pintype "passive"))
      (node (ref "U6") (pin "3") (pinfunction "VBAT_3") (pintype "passive"))
      (node (ref "VBAT2_TP") (pin "1") (pinfunction "1_1") (pintype "passive"))
    )
    (net (code "38") (name "VBAT3") (class "Default")
      (node (ref "BAT3") (pin "2") (pinfunction "2_2") (pintype "passive"))
      (node (ref "R10") (pin "2") (pinfunction "2_2") (pintype "passive"))
      (node (ref "U7") (pin "3") (pinfunction "VBAT_3") (pintype "passive"))
      (node (ref "VBAT3_TP") (pin "1") (pinfunction "1_1") (pintype "passive"))
    )
    (net (code "39") (name "VQ1") (class "Default")
      (node (ref "Q1") (pin "D") (pinfunction "D_D") (pintype "passive"))
      (node (ref "Q2") (pin "S") (pinfunction "S_S") (pintype "passive"))
      (node (ref "VQ1_TP") (pin "1") (pinfunction "1_1") (pintype "passive"))
    )
    (net (code "40") (name "VSW") (class "Default")
      (node (ref "C29") (pin "1") (pinfunction "1_1") (pintype "passive"))
      (node (ref "C30") (pin "1") (pinfunction "1_1") (pintype "passive"))
      (node (ref "C37") (pin "1") (pinfunction "1_1") (pintype "passive"))
      (node (ref "L4") (pin "1") (pinfunction "1_1") (pintype "passive"))
      (node (ref "Q2") (pin "D") (pinfunction "D_D") (pintype "passive"))
      (node (ref "R18") (pin "2") (pinfunction "2_2") (pintype "passive"))
      (node (ref "R24") (pin "2") (pinfunction "2_2") (pintype "passive"))
      (node (ref "U9") (pin "6") (pinfunction "IN_6") (pintype "power_in"))
      (node (ref "VSW_TP") (pin "1") (pinfunction "1_1") (pintype "passive"))
    )
    (net (code "41") (name "unconnected-(BAT1-Pad3)") (class "Default")
      (node (ref "BAT1") (pin "3") (pinfunction "3_3") (pintype "passive+no_connect"))
    )
    (net (code "42") (name "unconnected-(BAT2-Pad3)") (class "Default")
      (node (ref "BAT2") (pin "3") (pinfunction "3_3") (pintype "passive+no_connect"))
    )
    (net (code "43") (name "unconnected-(BAT3-Pad3)") (class "Default")
      (node (ref "BAT3") (pin "3") (pinfunction "3_3") (pintype "passive+no_connect"))
    )
    (net (code "44") (name "unconnected-(U8-NC-Pad4)") (class "Default")
      (node (ref "U8") (pin "4") (pinfunction "NC_4") (pintype "passive+no_connect"))
    )
  )
)
